# ZYF-02-0-R-8A8K64D4-SCH.net
KiCad netlist of a schematic drawn in EasyEDA
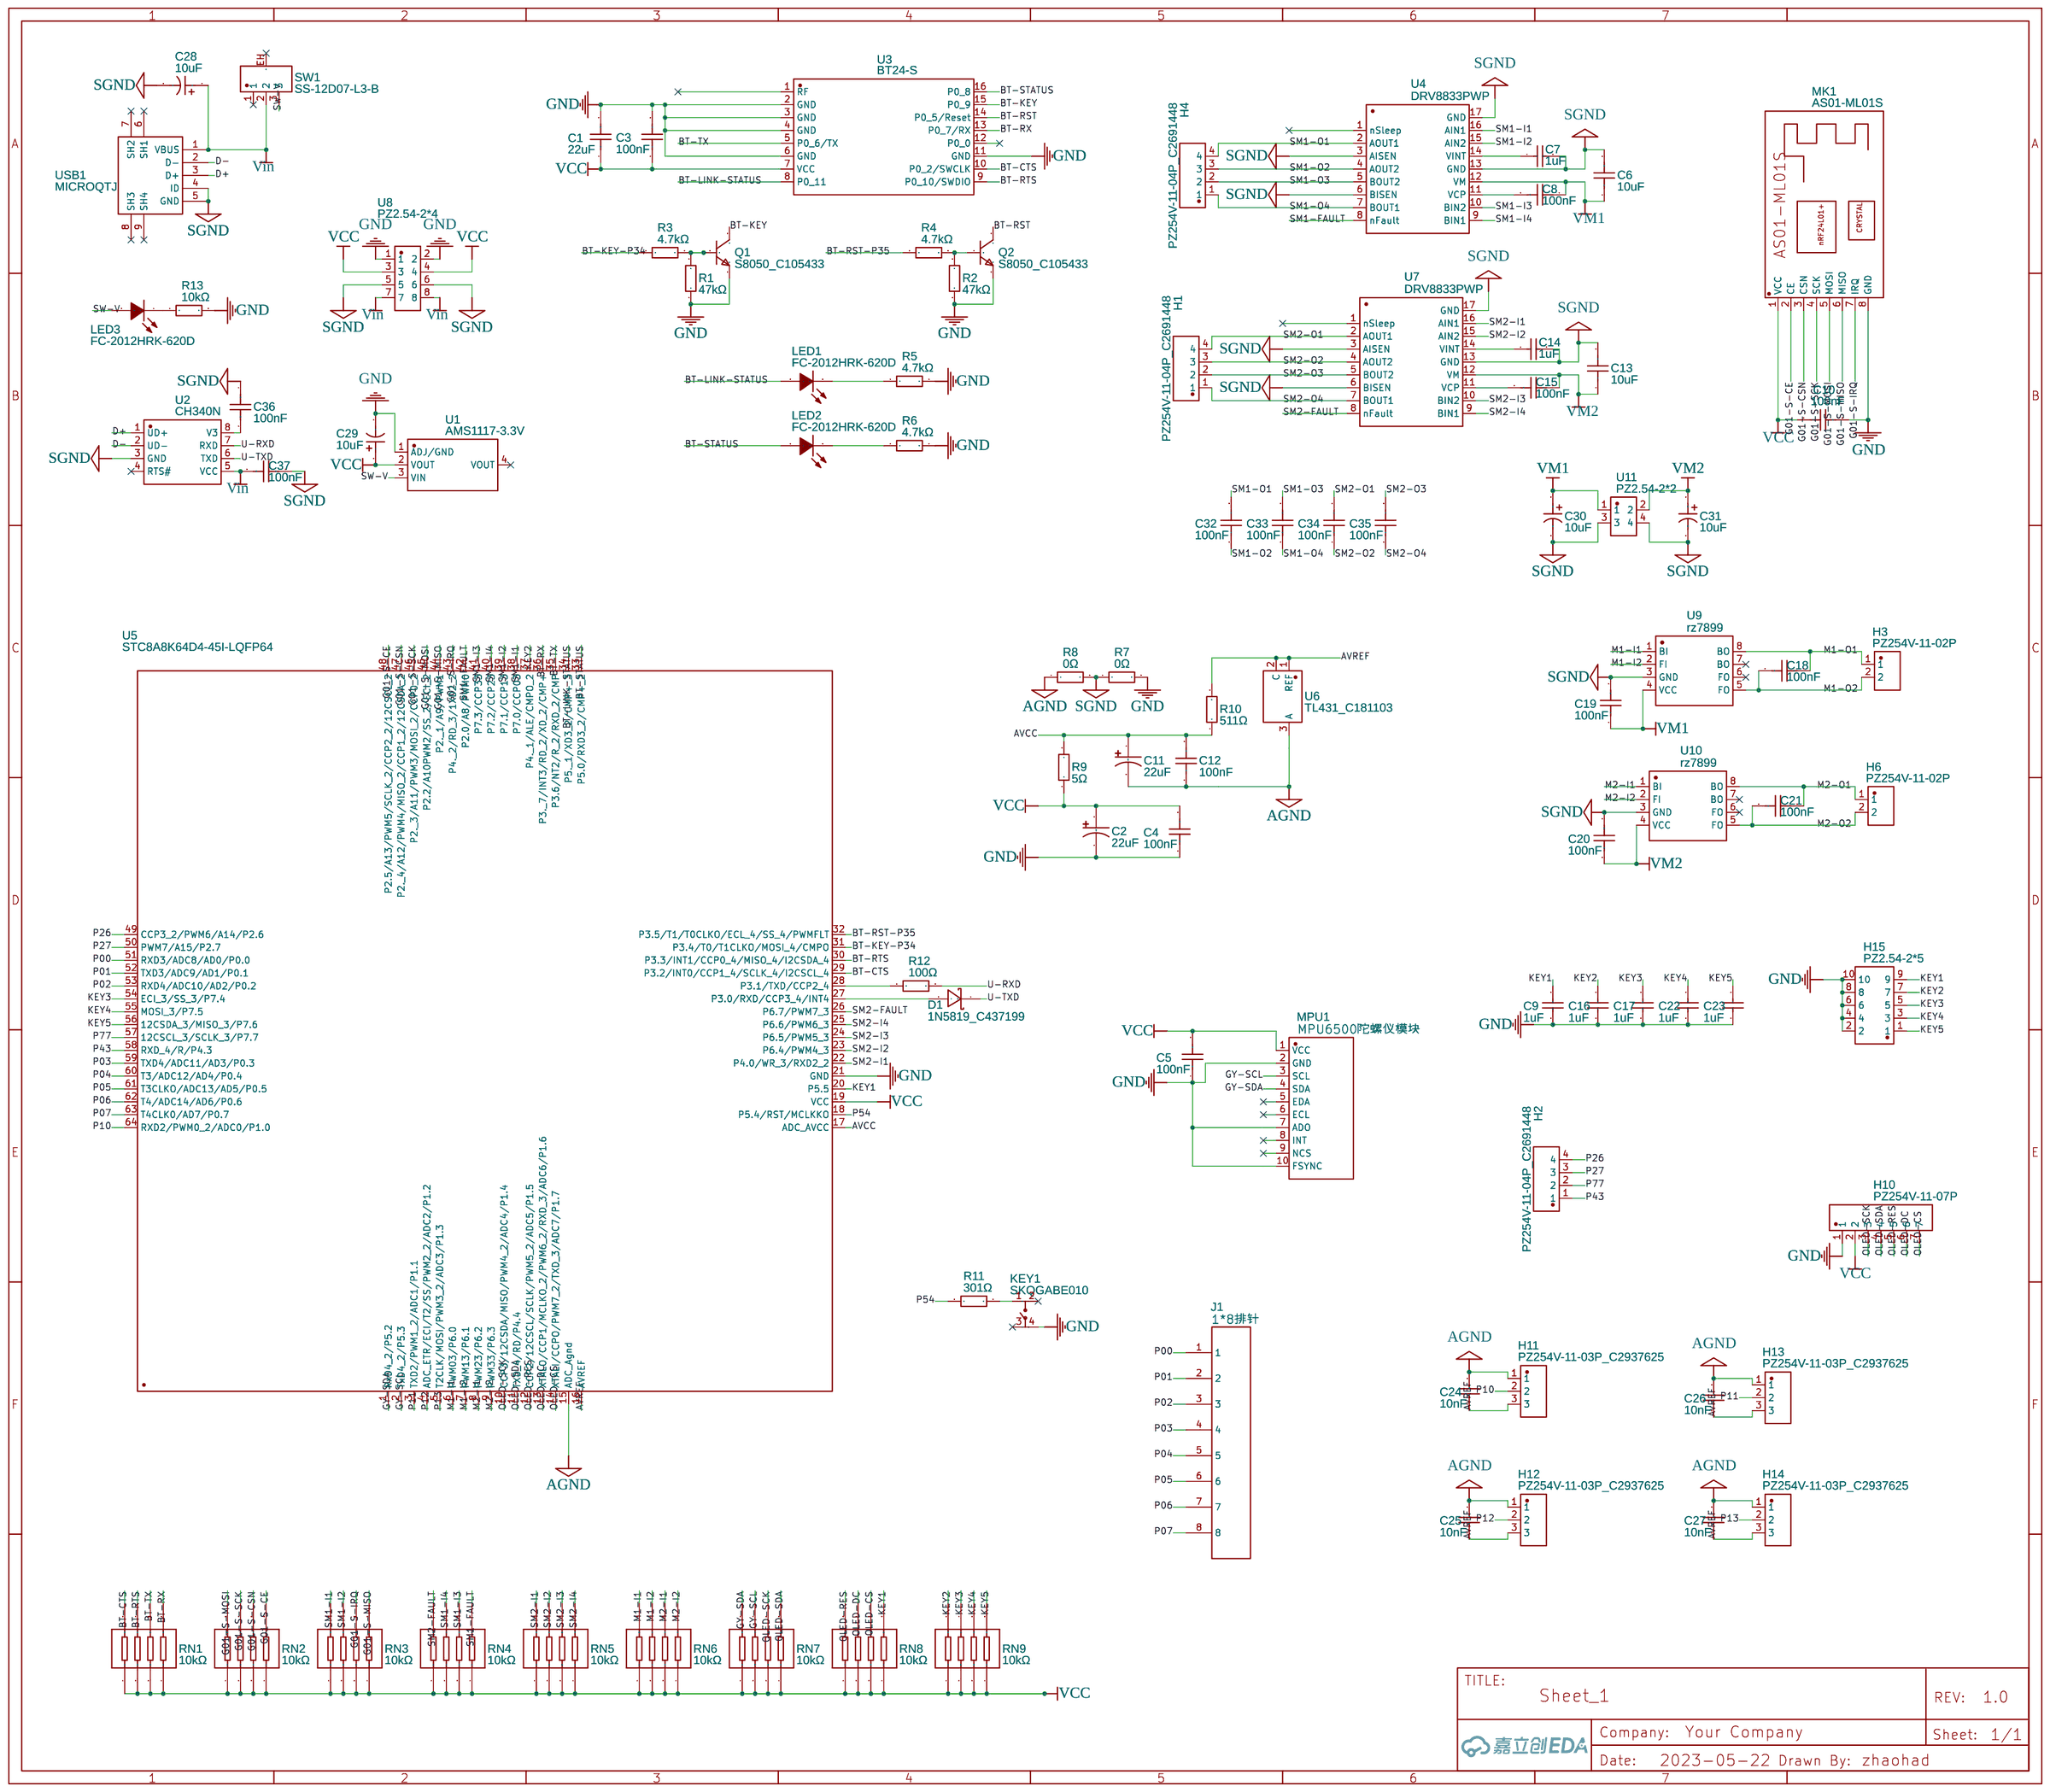
[diagram p0: schematic sheet]

(export (version "E")
  (design (tool "Eeschema 10.0.6"))
  (components
    (comp (ref "C1")
      (value "22uF")
      (fields
        (field (name "BOM_Manufacturer Part") "CL10A226MP8NUNE")
        (field (name "BOM_Supplier Part") "C86295")
      )
      (libsource (lib "") (part "CL10A226MP8NUNE"))
    )
    (comp (ref "C2")
      (value "22uF")
      (fields
        (field (name "BOM_Manufacturer Part") "EEEFTH101XAP")
        (field (name "BOM_Supplier Part") "C165974")
      )
      (libsource (lib "") (part "EEEFTH101XAP"))
    )
    (comp (ref "C3")
      (value "100nF")
      (fields
        (field (name "BOM_Manufacturer Part") "CC0603KRX7R9BB104")
        (field (name "BOM_Supplier Part") "C14663")
      )
      (libsource (lib "") (part "CC0603KRX7R9BB104_2"))
    )
    (comp (ref "C4")
      (value "100nF")
      (fields
        (field (name "BOM_Manufacturer Part") "CC0603KRX7R9BB104")
        (field (name "BOM_Supplier Part") "C14663")
      )
      (libsource (lib "") (part "CC0603KRX7R9BB104_2"))
    )
    (comp (ref "C5")
      (value "100nF")
      (fields
        (field (name "BOM_Manufacturer Part") "CC0603KRX7R9BB104")
        (field (name "BOM_Supplier Part") "C14663")
      )
      (libsource (lib "") (part "CC0603KRX7R9BB104_2"))
    )
    (comp (ref "C6")
      (value "10uF")
      (fields
        (field (name "BOM_Manufacturer Part") "CL10A106MA8NRNC")
        (field (name "BOM_Supplier Part") "C96446")
      )
      (libsource (lib "") (part "CL10A106MA8NRNC"))
    )
    (comp (ref "C7")
      (value "1uF")
      (fields
        (field (name "BOM_Manufacturer Part") "CL10A105KB8NNNC")
        (field (name "BOM_Supplier Part") "C15849")
      )
      (libsource (lib "") (part "CL10A105KB8NNNC_1"))
    )
    (comp (ref "C8")
      (value "100nF")
      (fields
        (field (name "BOM_Manufacturer Part") "CC0603KRX7R9BB104")
        (field (name "BOM_Supplier Part") "C14663")
      )
      (libsource (lib "") (part "CC0603KRX7R9BB104"))
    )
    (comp (ref "C9")
      (value "1uF")
      (fields
        (field (name "BOM_Manufacturer Part") "CL10A105KB8NNNC")
        (field (name "BOM_Supplier Part") "C15849")
      )
      (libsource (lib "") (part "CL10A105KB8NNNC"))
    )
    (comp (ref "C10")
      (value "100nF")
      (fields
        (field (name "BOM_Manufacturer Part") "CC0603KRX7R9BB104")
        (field (name "BOM_Supplier Part") "C14663")
      )
      (libsource (lib "") (part "CC0603KRX7R9BB104"))
    )
    (comp (ref "C11")
      (value "22uF")
      (fields
        (field (name "BOM_Manufacturer Part") "EEEFTH101XAP")
        (field (name "BOM_Supplier Part") "C165974")
      )
      (libsource (lib "") (part "EEEFTH101XAP"))
    )
    (comp (ref "C12")
      (value "100nF")
      (fields
        (field (name "BOM_Manufacturer Part") "CC0603KRX7R9BB104")
        (field (name "BOM_Supplier Part") "C14663")
      )
      (libsource (lib "") (part "CC0603KRX7R9BB104_2"))
    )
    (comp (ref "C13")
      (value "10uF")
      (fields
        (field (name "BOM_Manufacturer Part") "CL10A106MA8NRNC")
        (field (name "BOM_Supplier Part") "C96446")
      )
      (libsource (lib "") (part "CL10A106MA8NRNC"))
    )
    (comp (ref "C14")
      (value "1uF")
      (fields
        (field (name "BOM_Manufacturer Part") "CL10A105KB8NNNC")
        (field (name "BOM_Supplier Part") "C15849")
      )
      (libsource (lib "") (part "CL10A105KB8NNNC_1"))
    )
    (comp (ref "C15")
      (value "100nF")
      (fields
        (field (name "BOM_Manufacturer Part") "CC0603KRX7R9BB104")
        (field (name "BOM_Supplier Part") "C14663")
      )
      (libsource (lib "") (part "CC0603KRX7R9BB104"))
    )
    (comp (ref "C16")
      (value "1uF")
      (fields
        (field (name "BOM_Manufacturer Part") "CL10A105KB8NNNC")
        (field (name "BOM_Supplier Part") "C15849")
      )
      (libsource (lib "") (part "CL10A105KB8NNNC"))
    )
    (comp (ref "C17")
      (value "1uF")
      (fields
        (field (name "BOM_Manufacturer Part") "CL10A105KB8NNNC")
        (field (name "BOM_Supplier Part") "C15849")
      )
      (libsource (lib "") (part "CL10A105KB8NNNC"))
    )
    (comp (ref "C18")
      (value "100nF")
      (fields
        (field (name "BOM_Manufacturer Part") "CC0603KRX7R9BB104")
        (field (name "BOM_Supplier Part") "C14663")
      )
      (libsource (lib "") (part "CC0603KRX7R9BB104"))
    )
    (comp (ref "C19")
      (value "100nF")
      (fields
        (field (name "BOM_Manufacturer Part") "CC0603KRX7R9BB104")
        (field (name "BOM_Supplier Part") "C14663")
      )
      (libsource (lib "") (part "CC0603KRX7R9BB104_2"))
    )
    (comp (ref "C20")
      (value "100nF")
      (fields
        (field (name "BOM_Manufacturer Part") "CC0603KRX7R9BB104")
        (field (name "BOM_Supplier Part") "C14663")
      )
      (libsource (lib "") (part "CC0603KRX7R9BB104_2"))
    )
    (comp (ref "C21")
      (value "100nF")
      (fields
        (field (name "BOM_Manufacturer Part") "CC0603KRX7R9BB104")
        (field (name "BOM_Supplier Part") "C14663")
      )
      (libsource (lib "") (part "CC0603KRX7R9BB104"))
    )
    (comp (ref "C22")
      (value "1uF")
      (fields
        (field (name "BOM_Manufacturer Part") "CL10A105KB8NNNC")
        (field (name "BOM_Supplier Part") "C15849")
      )
      (libsource (lib "") (part "CL10A105KB8NNNC"))
    )
    (comp (ref "C23")
      (value "1uF")
      (fields
        (field (name "BOM_Manufacturer Part") "CL10A105KB8NNNC")
        (field (name "BOM_Supplier Part") "C15849")
      )
      (libsource (lib "") (part "CL10A105KB8NNNC"))
    )
    (comp (ref "C24")
      (value "10nF")
      (fields
        (field (name "BOM_Manufacturer Part") "CL10A105KB8NNNC")
        (field (name "BOM_Supplier Part") "C15849")
      )
      (libsource (lib "") (part "CL10A105KB8NNNC"))
    )
    (comp (ref "C25")
      (value "10nF")
      (fields
        (field (name "BOM_Manufacturer Part") "CL10A105KB8NNNC")
        (field (name "BOM_Supplier Part") "C15849")
      )
      (libsource (lib "") (part "CL10A105KB8NNNC"))
    )
    (comp (ref "C26")
      (value "10nF")
      (fields
        (field (name "BOM_Manufacturer Part") "CL10A105KB8NNNC")
        (field (name "BOM_Supplier Part") "C15849")
      )
      (libsource (lib "") (part "CL10A105KB8NNNC"))
    )
    (comp (ref "C27")
      (value "10nF")
      (fields
        (field (name "BOM_Manufacturer Part") "CL10A105KB8NNNC")
        (field (name "BOM_Supplier Part") "C15849")
      )
      (libsource (lib "") (part "CL10A105KB8NNNC"))
    )
    (comp (ref "C28")
      (value "10uF")
      (fields
        (field (name "BOM_Manufacturer Part") "XT10UF50V90RV0071")
        (field (name "BOM_Supplier Part") "C2992603")
      )
      (libsource (lib "") (part "XT10UF50V90RV0071"))
    )
    (comp (ref "C29")
      (value "10uF")
      (fields
        (field (name "BOM_Manufacturer Part") "XT10UF50V90RV0071")
        (field (name "BOM_Supplier Part") "C2992603")
      )
      (libsource (lib "") (part "XT10UF50V90RV0071_1"))
    )
    (comp (ref "C30")
      (value "10uF")
      (fields
        (field (name "BOM_Manufacturer Part") "XT10UF50V90RV0071")
        (field (name "BOM_Supplier Part") "C2992603")
      )
      (libsource (lib "") (part "XT10UF50V90RV0071_2"))
    )
    (comp (ref "C31")
      (value "10uF")
      (fields
        (field (name "BOM_Manufacturer Part") "XT10UF50V90RV0071")
        (field (name "BOM_Supplier Part") "C2992603")
      )
      (libsource (lib "") (part "XT10UF50V90RV0071_2"))
    )
    (comp (ref "C32")
      (value "100nF")
      (fields
        (field (name "BOM_Manufacturer Part") "CC0603KRX7R9BB104")
        (field (name "BOM_Supplier Part") "C14663")
      )
      (libsource (lib "") (part "CC0603KRX7R9BB104_2"))
    )
    (comp (ref "C33")
      (value "100nF")
      (fields
        (field (name "BOM_Manufacturer Part") "CC0603KRX7R9BB104")
        (field (name "BOM_Supplier Part") "C14663")
      )
      (libsource (lib "") (part "CC0603KRX7R9BB104_2"))
    )
    (comp (ref "C34")
      (value "100nF")
      (fields
        (field (name "BOM_Manufacturer Part") "CC0603KRX7R9BB104")
        (field (name "BOM_Supplier Part") "C14663")
      )
      (libsource (lib "") (part "CC0603KRX7R9BB104_2"))
    )
    (comp (ref "C35")
      (value "100nF")
      (fields
        (field (name "BOM_Manufacturer Part") "CC0603KRX7R9BB104")
        (field (name "BOM_Supplier Part") "C14663")
      )
      (libsource (lib "") (part "CC0603KRX7R9BB104_2"))
    )
    (comp (ref "C36")
      (value "100nF")
      (fields
        (field (name "BOM_Manufacturer Part") "CC0603KRX7R9BB104")
        (field (name "BOM_Supplier Part") "C14663")
      )
      (libsource (lib "") (part "CC0603KRX7R9BB104_1"))
    )
    (comp (ref "C37")
      (value "100nF")
      (fields
        (field (name "BOM_Manufacturer Part") "CC0603KRX7R9BB104")
        (field (name "BOM_Supplier Part") "C14663")
      )
      (libsource (lib "") (part "CC0603KRX7R9BB104"))
    )
    (comp (ref "D1")
      (value "1N5819_C437199")
      (fields (field (name "BOM_Manufacturer Part") "1N5819") (field (name "BOM_Supplier Part") "C437199"))
      (libsource (lib "") (part "1N5819_C437199"))
    )
    (comp (ref "H1")
      (value "PZ254V-11-04P_C2691448")
      (fields
        (field (name "BOM_Manufacturer Part") "PZ254V-11-04P")
        (field (name "BOM_Supplier Part") "C2691448")
      )
      (libsource (lib "") (part "PZ254V-11-04P_C2691448"))
    )
    (comp (ref "H2")
      (value "PZ254V-11-04P_C2691448")
      (fields
        (field (name "BOM_Manufacturer Part") "PZ254V-11-04P")
        (field (name "BOM_Supplier Part") "C2691448")
      )
      (libsource (lib "") (part "PZ254V-11-04P_C2691448"))
    )
    (comp (ref "H3")
      (value "PZ254V-11-02P")
      (fields (field (name "BOM_Supplier Part") "C492401"))
      (libsource (lib "") (part "PZ254V-11-02P"))
    )
    (comp (ref "H4")
      (value "PZ254V-11-04P_C2691448")
      (fields
        (field (name "BOM_Manufacturer Part") "PZ254V-11-04P")
        (field (name "BOM_Supplier Part") "C2691448")
      )
      (libsource (lib "") (part "PZ254V-11-04P_C2691448"))
    )
    (comp (ref "H6")
      (value "PZ254V-11-02P")
      (fields (field (name "BOM_Supplier Part") "C492401"))
      (libsource (lib "") (part "PZ254V-11-02P"))
    )
    (comp (ref "H10")
      (value "PZ254V-11-07P")
      (fields (field (name "BOM_Supplier Part") "C492406"))
      (libsource (lib "") (part "PZ254V-11-07P"))
    )
    (comp (ref "H11")
      (value "PZ254V-11-03P_C2937625")
      (fields
        (field (name "BOM_Manufacturer Part") "PZ254V-11-03P")
        (field (name "BOM_Supplier Part") "C2937625")
      )
      (libsource (lib "") (part "PZ254V-11-03P_C2937625"))
    )
    (comp (ref "H12")
      (value "PZ254V-11-03P_C2937625")
      (fields
        (field (name "BOM_Manufacturer Part") "PZ254V-11-03P")
        (field (name "BOM_Supplier Part") "C2937625")
      )
      (libsource (lib "") (part "PZ254V-11-03P_C2937625"))
    )
    (comp (ref "H13")
      (value "PZ254V-11-03P_C2937625")
      (fields
        (field (name "BOM_Manufacturer Part") "PZ254V-11-03P")
        (field (name "BOM_Supplier Part") "C2937625")
      )
      (libsource (lib "") (part "PZ254V-11-03P_C2937625"))
    )
    (comp (ref "H14")
      (value "PZ254V-11-03P_C2937625")
      (fields
        (field (name "BOM_Manufacturer Part") "PZ254V-11-03P")
        (field (name "BOM_Supplier Part") "C2937625")
      )
      (libsource (lib "") (part "PZ254V-11-03P_C2937625"))
    )
    (comp (ref "H15")
      (value "PZ2.54-2*5")
      (fields (field (name "BOM_Supplier Part") "C5156677"))
      (libsource (lib "") (part "PZ2.54-2*5"))
    )
    (comp (ref "J1")
      (value "1*8排针")
      (fields (field (name "BOM_Manufacturer Part") "2.54-1*8") (field (name "BOM_Supplier Part") "C5156616"))
      (libsource (lib "") (part "1*8排针"))
    )
    (comp (ref "KEY1")
      (value "SKQGABE010")
      (fields (field (name "BOM_Supplier Part") "C115351"))
      (libsource (lib "") (part "SKQGABE010"))
    )
    (comp (ref "LED1")
      (value "FC-2012HRK-620D")
      (fields (field (name "BOM_Manufacturer Part") "NCD0805R1") (field (name "BOM_Supplier Part") "C84256"))
      (libsource (lib "") (part "FC-2012HRK-620D"))
    )
    (comp (ref "LED2")
      (value "FC-2012HRK-620D")
      (fields (field (name "BOM_Manufacturer Part") "NCD0805R1") (field (name "BOM_Supplier Part") "C84256"))
      (libsource (lib "") (part "FC-2012HRK-620D"))
    )
    (comp (ref "LED3")
      (value "FC-2012HRK-620D")
      (fields (field (name "BOM_Manufacturer Part") "NCD0805R1") (field (name "BOM_Supplier Part") "C84256"))
      (libsource (lib "") (part "FC-2012HRK-620D"))
    )
    (comp (ref "MK1")
      (value "AS01-ML01S")
      (fields (field (name "BOM_Supplier Part") "C84802"))
      (libsource (lib "") (part "AS01-ML01S"))
    )
    (comp (ref "MPU1") (value "MPU6500陀螺仪模块") (libsource (lib "") (part "MPU6500陀螺仪模块")))
    (comp (ref "Q1")
      (value "S8050_C105433")
      (fields (field (name "BOM_Manufacturer Part") "S8050") (field (name "BOM_Supplier Part") "C105433"))
      (libsource (lib "") (part "S8050_C105433"))
    )
    (comp (ref "Q2")
      (value "S8050_C105433")
      (fields (field (name "BOM_Manufacturer Part") "S8050") (field (name "BOM_Supplier Part") "C105433"))
      (libsource (lib "") (part "S8050_C105433"))
    )
    (comp (ref "R1")
      (value "47kΩ")
      (fields
        (field (name "BOM_Manufacturer Part") "0603WAF4702T5E")
        (field (name "BOM_Supplier Part") "C25819")
      )
      (libsource (lib "") (part "0603WAF4702T5E"))
    )
    (comp (ref "R2")
      (value "47kΩ")
      (fields
        (field (name "BOM_Manufacturer Part") "0603WAF4702T5E")
        (field (name "BOM_Supplier Part") "C25819")
      )
      (libsource (lib "") (part "0603WAF4702T5E"))
    )
    (comp (ref "R3")
      (value "4.7kΩ")
      (fields
        (field (name "BOM_Manufacturer Part") "0603WAF4701T5E")
        (field (name "BOM_Supplier Part") "C23162")
      )
      (libsource (lib "") (part "0603WAF4701T5E"))
    )
    (comp (ref "R4")
      (value "4.7kΩ")
      (fields
        (field (name "BOM_Manufacturer Part") "0603WAF4701T5E")
        (field (name "BOM_Supplier Part") "C23162")
      )
      (libsource (lib "") (part "0603WAF4701T5E"))
    )
    (comp (ref "R5")
      (value "4.7kΩ")
      (fields
        (field (name "BOM_Manufacturer Part") "0603WAF4701T5E")
        (field (name "BOM_Supplier Part") "C23162")
      )
      (libsource (lib "") (part "0603WAF4701T5E"))
    )
    (comp (ref "R6")
      (value "4.7kΩ")
      (fields
        (field (name "BOM_Manufacturer Part") "0603WAF4701T5E")
        (field (name "BOM_Supplier Part") "C23162")
      )
      (libsource (lib "") (part "0603WAF4701T5E"))
    )
    (comp (ref "R7")
      (value "0Ω")
      (fields
        (field (name "BOM_Manufacturer Part") "0603WAF0000T5E")
        (field (name "BOM_Supplier Part") "C21189")
      )
      (libsource (lib "") (part "0603WAF0000T5E"))
    )
    (comp (ref "R8")
      (value "0Ω")
      (fields
        (field (name "BOM_Manufacturer Part") "0603WAF0000T5E")
        (field (name "BOM_Supplier Part") "C21189")
      )
      (libsource (lib "") (part "0603WAF0000T5E"))
    )
    (comp (ref "R9")
      (value "5Ω")
      (fields
        (field (name "BOM_Manufacturer Part") "0603WAF4701T5E")
        (field (name "BOM_Supplier Part") "C23162")
      )
      (libsource (lib "") (part "0603WAF4701T5E_1"))
    )
    (comp (ref "R10")
      (value "511Ω")
      (fields
        (field (name "BOM_Manufacturer Part") "0603WAF5100T5E")
        (field (name "BOM_Supplier Part") "C23193")
      )
      (libsource (lib "") (part "0603WAF5100T5E"))
    )
    (comp (ref "R11")
      (value "301Ω")
      (fields
        (field (name "BOM_Manufacturer Part") "0603WAF4701T5E")
        (field (name "BOM_Supplier Part") "C23162")
      )
      (libsource (lib "") (part "0603WAF4701T5E_2"))
    )
    (comp (ref "R12")
      (value "100Ω")
      (fields
        (field (name "BOM_Manufacturer Part") "0603WAF4701T5E")
        (field (name "BOM_Supplier Part") "C23162")
      )
      (libsource (lib "") (part "0603WAF4701T5E"))
    )
    (comp (ref "R13")
      (value "10kΩ")
      (fields
        (field (name "BOM_Manufacturer Part") "0603WAF4701T5E")
        (field (name "BOM_Supplier Part") "C23162")
      )
      (libsource (lib "") (part "0603WAF4701T5E"))
    )
    (comp (ref "RN1")
      (value "10kΩ")
      (fields
        (field (name "BOM_Manufacturer Part") "4D03WGJ0103T5E")
        (field (name "BOM_Supplier Part") "C29718")
      )
      (libsource (lib "") (part "4D03WGJ0103T5E"))
    )
    (comp (ref "RN2")
      (value "10kΩ")
      (fields
        (field (name "BOM_Manufacturer Part") "4D03WGJ0103T5E")
        (field (name "BOM_Supplier Part") "C29718")
      )
      (libsource (lib "") (part "4D03WGJ0103T5E"))
    )
    (comp (ref "RN3")
      (value "10kΩ")
      (fields
        (field (name "BOM_Manufacturer Part") "4D03WGJ0103T5E")
        (field (name "BOM_Supplier Part") "C29718")
      )
      (libsource (lib "") (part "4D03WGJ0103T5E"))
    )
    (comp (ref "RN4")
      (value "10kΩ")
      (fields
        (field (name "BOM_Manufacturer Part") "4D03WGJ0103T5E")
        (field (name "BOM_Supplier Part") "C29718")
      )
      (libsource (lib "") (part "4D03WGJ0103T5E"))
    )
    (comp (ref "RN5")
      (value "10kΩ")
      (fields
        (field (name "BOM_Manufacturer Part") "4D03WGJ0103T5E")
        (field (name "BOM_Supplier Part") "C29718")
      )
      (libsource (lib "") (part "4D03WGJ0103T5E"))
    )
    (comp (ref "RN6")
      (value "10kΩ")
      (fields
        (field (name "BOM_Manufacturer Part") "4D03WGJ0103T5E")
        (field (name "BOM_Supplier Part") "C29718")
      )
      (libsource (lib "") (part "4D03WGJ0103T5E"))
    )
    (comp (ref "RN7")
      (value "10kΩ")
      (fields
        (field (name "BOM_Manufacturer Part") "4D03WGJ0103T5E")
        (field (name "BOM_Supplier Part") "C29718")
      )
      (libsource (lib "") (part "4D03WGJ0103T5E"))
    )
    (comp (ref "RN8")
      (value "10kΩ")
      (fields
        (field (name "BOM_Manufacturer Part") "4D03WGJ0103T5E")
        (field (name "BOM_Supplier Part") "C29718")
      )
      (libsource (lib "") (part "4D03WGJ0103T5E"))
    )
    (comp (ref "RN9")
      (value "10kΩ")
      (fields
        (field (name "BOM_Manufacturer Part") "4D03WGJ0103T5E")
        (field (name "BOM_Supplier Part") "C29718")
      )
      (libsource (lib "") (part "4D03WGJ0103T5E"))
    )
    (comp (ref "SW1")
      (value "SS-12D07-L3-B")
      (fields
        (field (name "BOM_Manufacturer Part") "SS12D07L3B")
        (field (name "BOM_Supplier Part") "C480343")
      )
      (libsource (lib "") (part "SS-12D07-L3-B"))
    )
    (comp (ref "U1")
      (value "AMS1117-3.3V")
      (fields (field (name "BOM_Supplier Part") "C2688239"))
      (libsource (lib "") (part "AMS1117-3.3V"))
    )
    (comp (ref "U2")
      (value "CH340N")
      (fields (field (name "BOM_Supplier Part") "C506813"))
      (libsource (lib "") (part "CH340N"))
    )
    (comp (ref "U3")
      (value "BT24-S")
      (fields (field (name "BOM_Supplier Part") "C9900007879"))
      (libsource (lib "") (part "BT24-S"))
    )
    (comp (ref "U4")
      (value "DRV8833PWP")
      (fields
        (field (name "BOM_Manufacturer Part") "DRV8833PWPR")
        (field (name "BOM_Supplier Part") "C50506")
      )
      (libsource (lib "") (part "DRV8833PWP"))
    )
    (comp (ref "U5")
      (value "STC8A8K64D4-45I-LQFP64")
      (fields (field (name "BOM_Supplier Part") "C9900000181"))
      (libsource (lib "") (part "STC8A8K64D4-45I-LQFP64"))
    )
    (comp (ref "U6")
      (value "TL431_C181103")
      (fields (field (name "BOM_Manufacturer Part") "TL431") (field (name "BOM_Supplier Part") "C181103"))
      (libsource (lib "") (part "TL431_C181103"))
    )
    (comp (ref "U7")
      (value "DRV8833PWP")
      (fields
        (field (name "BOM_Manufacturer Part") "DRV8833PWPR")
        (field (name "BOM_Supplier Part") "C50506")
      )
      (libsource (lib "") (part "DRV8833PWP"))
    )
    (comp (ref "U8")
      (value "PZ2.54-2*4")
      (fields (field (name "BOM_Supplier Part") "C5156676"))
      (libsource (lib "") (part "PZ2.54-2*4"))
    )
    (comp (ref "U9")
      (value "rz7899")
      (fields (field (name "BOM_Supplier Part") "C92373"))
      (libsource (lib "") (part "rz7899"))
    )
    (comp (ref "U10")
      (value "rz7899")
      (fields (field (name "BOM_Supplier Part") "C92373"))
      (libsource (lib "") (part "rz7899"))
    )
    (comp (ref "U11")
      (value "PZ2.54-2*2")
      (fields (field (name "BOM_Supplier Part") "C5156675"))
      (libsource (lib "") (part "PZ2.54-2*2"))
    )
    (comp (ref "USB1")
      (value "MICROQTJ")
      (fields (field (name "BOM_Manufacturer Part") "MicroQTJ") (field (name "BOM_Supplier Part") "C404968"))
      (libsource (lib "") (part "MICROQTJ"))
    )
  )
  (nets
    (net (code "1") (name "/AVCC") (class "Default")
      (node (ref "C11") (pin "1") (pinfunction "1_1") (pintype "unspecified"))
      (node (ref "C12") (pin "2") (pinfunction "2_2") (pintype "unspecified"))
      (node (ref "R10") (pin "1") (pinfunction "1_1") (pintype "input"))
      (node (ref "R9") (pin "2") (pinfunction "2_2") (pintype "input"))
      (node (ref "U5") (pin "17") (pinfunction "ADC_AVCC_17") (pintype "unspecified"))
    )
    (net (code "2") (name "/AVREF") (class "Default")
      (node (ref "C24") (pin "1") (pinfunction "1_1") (pintype "input"))
      (node (ref "C25") (pin "1") (pinfunction "1_1") (pintype "input"))
      (node (ref "C26") (pin "1") (pinfunction "1_1") (pintype "input"))
      (node (ref "C27") (pin "1") (pinfunction "1_1") (pintype "input"))
      (node (ref "H11") (pin "3") (pinfunction "3_3") (pintype "unspecified"))
      (node (ref "H12") (pin "3") (pinfunction "3_3") (pintype "unspecified"))
      (node (ref "H13") (pin "3") (pinfunction "3_3") (pintype "unspecified"))
      (node (ref "H14") (pin "3") (pinfunction "3_3") (pintype "unspecified"))
      (node (ref "R10") (pin "2") (pinfunction "2_2") (pintype "input"))
      (node (ref "U5") (pin "16") (pinfunction "AVREF_16") (pintype "unspecified"))
      (node (ref "U6") (pin "1") (pinfunction "REF_1") (pintype "unspecified"))
      (node (ref "U6") (pin "2") (pinfunction "C_2") (pintype "unspecified"))
    )
    (net (code "3") (name "/BT-CTS") (class "Default")
      (node (ref "RN1") (pin "8") (pinfunction "8_8") (pintype "input"))
      (node (ref "U3") (pin "10") (pinfunction "P0_2/SWCLK_10") (pintype "unspecified"))
      (node (ref "U5") (pin "29") (pinfunction "P3.2/INT0/CCP1_4/SCLK_4/I2CSCL_4_29") (pintype "unspecified"))
    )
    (net (code "4") (name "/BT-KEY") (class "Default")
      (node (ref "Q1") (pin "3") (pinfunction "3_3") (pintype "input"))
      (node (ref "U3") (pin "15") (pinfunction "P0_9_15") (pintype "unspecified"))
    )
    (net (code "5") (name "/BT-KEY-P34") (class "Default")
      (node (ref "R3") (pin "1") (pinfunction "1_1") (pintype "input"))
      (node (ref "U5") (pin "31") (pinfunction "P3.4/T0/T1CLKO/MOSI_4/CMPO_31") (pintype "unspecified"))
    )
    (net (code "6") (name "/BT-LINK-STATUS") (class "Default")
      (node (ref "LED1") (pin "2") (pinfunction "+_2") (pintype "unspecified"))
      (node (ref "U3") (pin "8") (pinfunction "P0_11_8") (pintype "unspecified"))
      (node (ref "U5") (pin "34") (pinfunction "P5._1/XD3_2/CMP+_3_34") (pintype "unspecified"))
    )
    (net (code "7") (name "/BT-RST") (class "Default")
      (node (ref "Q2") (pin "3") (pinfunction "3_3") (pintype "input"))
      (node (ref "U3") (pin "14") (pinfunction "P0_5/Reset_14") (pintype "unspecified"))
    )
    (net (code "8") (name "/BT-RST-P35") (class "Default")
      (node (ref "R4") (pin "1") (pinfunction "1_1") (pintype "input"))
      (node (ref "U5") (pin "32") (pinfunction "P3.5/T1/T0CLKO/ECL_4/SS_4/PWMFLT_32") (pintype "unspecified"))
    )
    (net (code "9") (name "/BT-RTS") (class "Default")
      (node (ref "RN1") (pin "7") (pinfunction "7_7") (pintype "input"))
      (node (ref "U3") (pin "9") (pinfunction "P0_10/SWDIO_9") (pintype "unspecified"))
      (node (ref "U5") (pin "30") (pinfunction "P3.3/INT1/CCP0_4/MISO_4/I2CSDA_4_30") (pintype "unspecified"))
    )
    (net (code "10") (name "/BT-RX") (class "Default")
      (node (ref "RN1") (pin "5") (pinfunction "5_5") (pintype "input"))
      (node (ref "U3") (pin "13") (pinfunction "P0_7/RX_13") (pintype "unspecified"))
      (node (ref "U5") (pin "36") (pinfunction "P3._7/INT3/RD_2/XD_2/CMP+_36") (pintype "unspecified"))
    )
    (net (code "11") (name "/BT-STATUS") (class "Default")
      (node (ref "LED2") (pin "2") (pinfunction "+_2") (pintype "unspecified"))
      (node (ref "U3") (pin "16") (pinfunction "P0_8_16") (pintype "unspecified"))
      (node (ref "U5") (pin "33") (pinfunction "P5.0/RXD3_2/CMP+_2_33") (pintype "unspecified"))
    )
    (net (code "12") (name "/BT-TX") (class "Default")
      (node (ref "RN1") (pin "6") (pinfunction "6_6") (pintype "input"))
      (node (ref "U3") (pin "5") (pinfunction "P0_6/TX_5") (pintype "unspecified"))
      (node (ref "U5") (pin "35") (pinfunction "P3.6/NT2/R_2/RXD_2/CMP_35") (pintype "unspecified"))
    )
    (net (code "13") (name "/D+") (class "Default")
      (node (ref "U2") (pin "1") (pinfunction "UD+_1") (pintype "unspecified"))
      (node (ref "USB1") (pin "3") (pinfunction "D+_3") (pintype "unspecified"))
    )
    (net (code "14") (name "/D-") (class "Default")
      (node (ref "U2") (pin "2") (pinfunction "UD-_2") (pintype "unspecified"))
      (node (ref "USB1") (pin "2") (pinfunction "D-_2") (pintype "unspecified"))
    )
    (net (code "15") (name "/G01-S-CE") (class "Default")
      (node (ref "MK1") (pin "2") (pinfunction "CE_2") (pintype "unspecified"))
      (node (ref "RN2") (pin "5") (pinfunction "5_5") (pintype "input"))
      (node (ref "U5") (pin "48") (pinfunction "P2.5/A13/PWM5/SCLK_2/CCP2_2/12CSCL_2_48") (pintype "unspecified"))
    )
    (net (code "16") (name "/G01-S-CSN") (class "Default")
      (node (ref "MK1") (pin "3") (pinfunction "CSN_3") (pintype "unspecified"))
      (node (ref "RN2") (pin "6") (pinfunction "6_6") (pintype "input"))
      (node (ref "U5") (pin "47") (pinfunction "P2._4/A12/PWM4/MISO_2/CCP1_2/12CSDA_2_47") (pintype "unspecified"))
    )
    (net (code "17") (name "/G01-S-IRQ") (class "Default")
      (node (ref "MK1") (pin "7") (pinfunction "IRQ_7") (pintype "unspecified"))
      (node (ref "RN3") (pin "6") (pinfunction "6_6") (pintype "input"))
      (node (ref "U5") (pin "43") (pinfunction "P4._2/RD_3/1XD2_2_43") (pintype "unspecified"))
    )
    (net (code "18") (name "/G01-S-MISO") (class "Default")
      (node (ref "MK1") (pin "6") (pinfunction "MISO_6") (pintype "unspecified"))
      (node (ref "RN3") (pin "5") (pinfunction "5_5") (pintype "input"))
      (node (ref "U5") (pin "44") (pinfunction "P2._1/A9/PWM1_44") (pintype "unspecified"))
    )
    (net (code "19") (name "/G01-S-MOSI") (class "Default")
      (node (ref "MK1") (pin "5") (pinfunction "MOSI_5") (pintype "unspecified"))
      (node (ref "RN2") (pin "8") (pinfunction "8_8") (pintype "input"))
      (node (ref "U5") (pin "45") (pinfunction "P2.2/A10PWM2/SS_2/ECI_2_45") (pintype "unspecified"))
    )
    (net (code "20") (name "/G01-S-SCK") (class "Default")
      (node (ref "MK1") (pin "4") (pinfunction "SCK_4") (pintype "unspecified"))
      (node (ref "RN2") (pin "7") (pinfunction "7_7") (pintype "input"))
      (node (ref "U5") (pin "46") (pinfunction "P2._3/A11/PWM3/MOSI_2/CCP0_2_46") (pintype "unspecified"))
    )
    (net (code "21") (name "/GY-SCL") (class "Default")
      (node (ref "MPU1") (pin "3") (pinfunction "SCL_3") (pintype "unspecified"))
      (node (ref "RN7") (pin "7") (pinfunction "7_7") (pintype "input"))
      (node (ref "U5") (pin "2") (pinfunction "TxD4_2/P5.3_2") (pintype "unspecified"))
    )
    (net (code "22") (name "/GY-SDA") (class "Default")
      (node (ref "MPU1") (pin "4") (pinfunction "SDA_4") (pintype "unspecified"))
      (node (ref "RN7") (pin "8") (pinfunction "8_8") (pintype "input"))
      (node (ref "U5") (pin "1") (pinfunction "RxD4_2/P5.2_1") (pintype "unspecified"))
    )
    (net (code "23") (name "/KEY1") (class "Default")
      (node (ref "C9") (pin "2") (pinfunction "2_2") (pintype "input"))
      (node (ref "H15") (pin "9") (pinfunction "9_9") (pintype "unspecified"))
      (node (ref "RN8") (pin "5") (pinfunction "5_5") (pintype "input"))
      (node (ref "U5") (pin "20") (pinfunction "P5.5_20") (pintype "unspecified"))
    )
    (net (code "24") (name "/KEY2") (class "Default")
      (node (ref "C16") (pin "2") (pinfunction "2_2") (pintype "input"))
      (node (ref "H15") (pin "7") (pinfunction "7_7") (pintype "unspecified"))
      (node (ref "RN9") (pin "8") (pinfunction "8_8") (pintype "input"))
      (node (ref "U5") (pin "37") (pinfunction "P4._1/ALE/CMPO_2_37") (pintype "unspecified"))
    )
    (net (code "25") (name "/KEY3") (class "Default")
      (node (ref "C17") (pin "2") (pinfunction "2_2") (pintype "input"))
      (node (ref "H15") (pin "5") (pinfunction "5_5") (pintype "unspecified"))
      (node (ref "RN9") (pin "7") (pinfunction "7_7") (pintype "input"))
      (node (ref "U5") (pin "54") (pinfunction "ECI_3/SS_3/P7.4_54") (pintype "unspecified"))
    )
    (net (code "26") (name "/KEY4") (class "Default")
      (node (ref "C22") (pin "2") (pinfunction "2_2") (pintype "input"))
      (node (ref "H15") (pin "3") (pinfunction "3_3") (pintype "unspecified"))
      (node (ref "RN9") (pin "6") (pinfunction "6_6") (pintype "input"))
      (node (ref "U5") (pin "55") (pinfunction "MOSI_3/P7.5_55") (pintype "unspecified"))
    )
    (net (code "27") (name "/KEY5") (class "Default")
      (node (ref "C23") (pin "2") (pinfunction "2_2") (pintype "input"))
      (node (ref "H15") (pin "1") (pinfunction "1_1") (pintype "unspecified"))
      (node (ref "RN9") (pin "5") (pinfunction "5_5") (pintype "input"))
      (node (ref "U5") (pin "56") (pinfunction "12CSDA_3/MISO_3/P7.6_56") (pintype "unspecified"))
    )
    (net (code "28") (name "/M1-I1") (class "Default")
      (node (ref "RN6") (pin "8") (pinfunction "8_8") (pintype "input"))
      (node (ref "U5") (pin "6") (pinfunction "PWM03/P6.0_6") (pintype "unspecified"))
      (node (ref "U9") (pin "1") (pinfunction "BI_1") (pintype "unspecified"))
    )
    (net (code "29") (name "/M1-I2") (class "Default")
      (node (ref "RN6") (pin "7") (pinfunction "7_7") (pintype "input"))
      (node (ref "U5") (pin "7") (pinfunction "PWM13/P6.1_7") (pintype "unspecified"))
      (node (ref "U9") (pin "2") (pinfunction "FI_2") (pintype "unspecified"))
    )
    (net (code "30") (name "/M1-O1") (class "Default")
      (node (ref "C18") (pin "1") (pinfunction "1_1") (pintype "unspecified"))
      (node (ref "H3") (pin "1") (pinfunction "1_1") (pintype "unspecified"))
      (node (ref "U9") (pin "8") (pinfunction "BO_8") (pintype "unspecified"))
    )
    (net (code "31") (name "/M1-O2") (class "Default")
      (node (ref "C18") (pin "2") (pinfunction "2_2") (pintype "unspecified"))
      (node (ref "H3") (pin "2") (pinfunction "2_2") (pintype "unspecified"))
      (node (ref "U9") (pin "5") (pinfunction "FO_5") (pintype "unspecified"))
    )
    (net (code "32") (name "/M2-I1") (class "Default")
      (node (ref "RN6") (pin "6") (pinfunction "6_6") (pintype "input"))
      (node (ref "U10") (pin "1") (pinfunction "BI_1") (pintype "unspecified"))
      (node (ref "U5") (pin "8") (pinfunction "PWM23/P6.2_8") (pintype "unspecified"))
    )
    (net (code "33") (name "/M2-I2") (class "Default")
      (node (ref "RN6") (pin "5") (pinfunction "5_5") (pintype "input"))
      (node (ref "U10") (pin "2") (pinfunction "FI_2") (pintype "unspecified"))
      (node (ref "U5") (pin "9") (pinfunction "PWM33/P6.3_9") (pintype "unspecified"))
    )
    (net (code "34") (name "/M2-O1") (class "Default")
      (node (ref "C21") (pin "1") (pinfunction "1_1") (pintype "unspecified"))
      (node (ref "H6") (pin "1") (pinfunction "1_1") (pintype "unspecified"))
      (node (ref "U10") (pin "8") (pinfunction "BO_8") (pintype "unspecified"))
    )
    (net (code "35") (name "/M2-O2") (class "Default")
      (node (ref "C21") (pin "2") (pinfunction "2_2") (pintype "unspecified"))
      (node (ref "H6") (pin "2") (pinfunction "2_2") (pintype "unspecified"))
      (node (ref "U10") (pin "5") (pinfunction "FO_5") (pintype "unspecified"))
    )
    (net (code "36") (name "/OLED-CS") (class "Default")
      (node (ref "H10") (pin "7") (pinfunction "7_7") (pintype "unspecified"))
      (node (ref "RN8") (pin "6") (pinfunction "6_6") (pintype "input"))
      (node (ref "U5") (pin "14") (pinfunction "XTALI/CCPO/PWM7_2/TXD_3/ADC7/P1.7_14") (pintype "unspecified"))
    )
    (net (code "37") (name "/OLED-DC") (class "Default")
      (node (ref "H10") (pin "6") (pinfunction "6_6") (pintype "unspecified"))
      (node (ref "RN8") (pin "7") (pinfunction "7_7") (pintype "input"))
      (node (ref "U5") (pin "13") (pinfunction "XTALO/CCP1/MCLKO_2/PWM6_2/RXD_3/ADC6/P1.6_13") (pintype "unspecified"))
    )
    (net (code "38") (name "/OLED-RES") (class "Default")
      (node (ref "H10") (pin "5") (pinfunction "5_5") (pintype "unspecified"))
      (node (ref "RN8") (pin "8") (pinfunction "8_8") (pintype "input"))
      (node (ref "U5") (pin "12") (pinfunction "CCP2/12CSCL/SCLK/PWM5_2/ADC5/P1.5_12") (pintype "unspecified"))
    )
    (net (code "39") (name "/OLED-SCK") (class "Default")
      (node (ref "H10") (pin "3") (pinfunction "3_3") (pintype "unspecified"))
      (node (ref "RN7") (pin "6") (pinfunction "6_6") (pintype "input"))
      (node (ref "U5") (pin "10") (pinfunction "CCP3/12CSDA/MISO/PWM4_2/ADC4/P1.4_10") (pintype "unspecified"))
    )
    (net (code "40") (name "/OLED-SDA") (class "Default")
      (node (ref "H10") (pin "4") (pinfunction "4_4") (pintype "unspecified"))
      (node (ref "RN7") (pin "5") (pinfunction "5_5") (pintype "input"))
      (node (ref "U5") (pin "11") (pinfunction "TXD_4/RD/P4.4_11") (pintype "unspecified"))
    )
    (net (code "41") (name "/P00") (class "Default")
      (node (ref "J1") (pin "1") (pinfunction "1_1") (pintype "unspecified"))
      (node (ref "U5") (pin "51") (pinfunction "RXD3/ADC8/AD0/P0.0_51") (pintype "unspecified"))
    )
    (net (code "42") (name "/P01") (class "Default")
      (node (ref "J1") (pin "2") (pinfunction "2_2") (pintype "unspecified"))
      (node (ref "U5") (pin "52") (pinfunction "TXD3/ADC9/AD1/P0.1_52") (pintype "unspecified"))
    )
    (net (code "43") (name "/P02") (class "Default")
      (node (ref "J1") (pin "3") (pinfunction "3_3") (pintype "unspecified"))
      (node (ref "U5") (pin "53") (pinfunction "RXD4/ADC10/AD2/P0.2_53") (pintype "unspecified"))
    )
    (net (code "44") (name "/P03") (class "Default")
      (node (ref "J1") (pin "4") (pinfunction "4_4") (pintype "unspecified"))
      (node (ref "U5") (pin "59") (pinfunction "TXD4/ADC11/AD3/P0.3_59") (pintype "unspecified"))
    )
    (net (code "45") (name "/P04") (class "Default")
      (node (ref "J1") (pin "5") (pinfunction "5_5") (pintype "unspecified"))
      (node (ref "U5") (pin "60") (pinfunction "T3/ADC12/AD4/P0.4_60") (pintype "unspecified"))
    )
    (net (code "46") (name "/P05") (class "Default")
      (node (ref "J1") (pin "6") (pinfunction "6_6") (pintype "unspecified"))
      (node (ref "U5") (pin "61") (pinfunction "T3CLKO/ADC13/AD5/P0.5_61") (pintype "unspecified"))
    )
    (net (code "47") (name "/P06") (class "Default")
      (node (ref "J1") (pin "7") (pinfunction "7_7") (pintype "unspecified"))
      (node (ref "U5") (pin "62") (pinfunction "T4/ADC14/AD6/P0.6_62") (pintype "unspecified"))
    )
    (net (code "48") (name "/P07") (class "Default")
      (node (ref "J1") (pin "8") (pinfunction "8_8") (pintype "unspecified"))
      (node (ref "U5") (pin "63") (pinfunction "T4CLK0/AD7/P0.7_63") (pintype "unspecified"))
    )
    (net (code "49") (name "/P10") (class "Default")
      (node (ref "H11") (pin "2") (pinfunction "2_2") (pintype "unspecified"))
      (node (ref "U5") (pin "64") (pinfunction "RXD2/PWM0_2/ADC0/P1.0_64") (pintype "unspecified"))
    )
    (net (code "50") (name "/P11") (class "Default")
      (node (ref "H13") (pin "2") (pinfunction "2_2") (pintype "unspecified"))
      (node (ref "U5") (pin "3") (pinfunction "TXD2/PWM1_2/ADC1/P1.1_3") (pintype "unspecified"))
    )
    (net (code "51") (name "/P12") (class "Default")
      (node (ref "H12") (pin "2") (pinfunction "2_2") (pintype "unspecified"))
      (node (ref "U5") (pin "4") (pinfunction "ADC_ETR/ECI/T2/SS/PWM2_2/ADC2/P1.2_4") (pintype "unspecified"))
    )
    (net (code "52") (name "/P13") (class "Default")
      (node (ref "H14") (pin "2") (pinfunction "2_2") (pintype "unspecified"))
      (node (ref "U5") (pin "5") (pinfunction "T2CLK/MOSI/PWM3_2/ADC3/P1.3_5") (pintype "unspecified"))
    )
    (net (code "53") (name "/P26") (class "Default")
      (node (ref "H2") (pin "4") (pinfunction "4_4") (pintype "unspecified"))
      (node (ref "U5") (pin "49") (pinfunction "CCP3_2/PWM6/A14/P2.6_49") (pintype "unspecified"))
    )
    (net (code "54") (name "/P27") (class "Default")
      (node (ref "H2") (pin "3") (pinfunction "3_3") (pintype "unspecified"))
      (node (ref "U5") (pin "50") (pinfunction "PWM7/A15/P2.7_50") (pintype "unspecified"))
    )
    (net (code "55") (name "/P43") (class "Default")
      (node (ref "H2") (pin "1") (pinfunction "1_1") (pintype "unspecified"))
      (node (ref "U5") (pin "58") (pinfunction "RXD_4/R/P4.3_58") (pintype "unspecified"))
    )
    (net (code "56") (name "/P54") (class "Default")
      (node (ref "R11") (pin "2") (pinfunction "2_2") (pintype "input"))
      (node (ref "U5") (pin "18") (pinfunction "P5.4/RST/MCLKKO_18") (pintype "unspecified"))
    )
    (net (code "57") (name "/P77") (class "Default")
      (node (ref "H2") (pin "2") (pinfunction "2_2") (pintype "unspecified"))
      (node (ref "U5") (pin "57") (pinfunction "12CSCL_3/SCLK_3/P7.7_57") (pintype "unspecified"))
    )
    (net (code "58") (name "/SM1-FAULT") (class "Default")
      (node (ref "RN4") (pin "5") (pinfunction "5_5") (pintype "input"))
      (node (ref "U4") (pin "8") (pinfunction "nFault_8") (pintype "unspecified"))
      (node (ref "U5") (pin "42") (pinfunction "P2.0/A8/PWM0_42") (pintype "unspecified"))
    )
    (net (code "59") (name "/SM1-I1") (class "Default")
      (node (ref "RN3") (pin "8") (pinfunction "8_8") (pintype "input"))
      (node (ref "U4") (pin "16") (pinfunction "AIN1_16") (pintype "unspecified"))
      (node (ref "U5") (pin "38") (pinfunction "P7.0/CCP03_38") (pintype "unspecified"))
    )
    (net (code "60") (name "/SM1-I2") (class "Default")
      (node (ref "RN3") (pin "7") (pinfunction "7_7") (pintype "input"))
      (node (ref "U4") (pin "15") (pinfunction "AIN2_15") (pintype "unspecified"))
      (node (ref "U5") (pin "39") (pinfunction "P7.1/CCP13_39") (pintype "unspecified"))
    )
    (net (code "61") (name "/SM1-I3") (class "Default")
      (node (ref "RN4") (pin "6") (pinfunction "6_6") (pintype "input"))
      (node (ref "U4") (pin "10") (pinfunction "BIN2_10") (pintype "unspecified"))
      (node (ref "U5") (pin "41") (pinfunction "P7.3/CCP33_41") (pintype "unspecified"))
    )
    (net (code "62") (name "/SM1-I4") (class "Default")
      (node (ref "RN4") (pin "7") (pinfunction "7_7") (pintype "input"))
      (node (ref "U4") (pin "9") (pinfunction "BIN1_9") (pintype "unspecified"))
      (node (ref "U5") (pin "40") (pinfunction "P7.2/CCP23_40") (pintype "unspecified"))
    )
    (net (code "63") (name "/SM1-O1") (class "Default")
      (node (ref "C32") (pin "2") (pinfunction "2_2") (pintype "unspecified"))
      (node (ref "H4") (pin "4") (pinfunction "4_4") (pintype "unspecified"))
      (node (ref "U4") (pin "2") (pinfunction "AOUT1_2") (pintype "unspecified"))
    )
    (net (code "64") (name "/SM1-O2") (class "Default")
      (node (ref "C32") (pin "1") (pinfunction "1_1") (pintype "unspecified"))
      (node (ref "H4") (pin "3") (pinfunction "3_3") (pintype "unspecified"))
      (node (ref "U4") (pin "4") (pinfunction "AOUT2_4") (pintype "unspecified"))
    )
    (net (code "65") (name "/SM1-O3") (class "Default")
      (node (ref "C33") (pin "2") (pinfunction "2_2") (pintype "unspecified"))
      (node (ref "H4") (pin "2") (pinfunction "2_2") (pintype "unspecified"))
      (node (ref "U4") (pin "5") (pinfunction "BOUT2_5") (pintype "unspecified"))
    )
    (net (code "66") (name "/SM1-O4") (class "Default")
      (node (ref "C33") (pin "1") (pinfunction "1_1") (pintype "unspecified"))
      (node (ref "H4") (pin "1") (pinfunction "1_1") (pintype "unspecified"))
      (node (ref "U4") (pin "7") (pinfunction "BOUT1_7") (pintype "unspecified"))
    )
    (net (code "67") (name "/SM2-FAULT") (class "Default")
      (node (ref "RN4") (pin "8") (pinfunction "8_8") (pintype "input"))
      (node (ref "U5") (pin "26") (pinfunction "P6.7/PWM7_3_26") (pintype "unspecified"))
      (node (ref "U7") (pin "8") (pinfunction "nFault_8") (pintype "unspecified"))
    )
    (net (code "68") (name "/SM2-I1") (class "Default")
      (node (ref "RN5") (pin "8") (pinfunction "8_8") (pintype "input"))
      (node (ref "U5") (pin "22") (pinfunction "P4.0/WR_3/RXD2_2_22") (pintype "unspecified"))
      (node (ref "U7") (pin "16") (pinfunction "AIN1_16") (pintype "unspecified"))
    )
    (net (code "69") (name "/SM2-I2") (class "Default")
      (node (ref "RN5") (pin "7") (pinfunction "7_7") (pintype "input"))
      (node (ref "U5") (pin "23") (pinfunction "P6.4/PWM4_3_23") (pintype "unspecified"))
      (node (ref "U7") (pin "15") (pinfunction "AIN2_15") (pintype "unspecified"))
    )
    (net (code "70") (name "/SM2-I3") (class "Default")
      (node (ref "RN5") (pin "6") (pinfunction "6_6") (pintype "input"))
      (node (ref "U5") (pin "24") (pinfunction "P6.5/PWM5_3_24") (pintype "unspecified"))
      (node (ref "U7") (pin "10") (pinfunction "BIN2_10") (pintype "unspecified"))
    )
    (net (code "71") (name "/SM2-I4") (class "Default")
      (node (ref "RN5") (pin "5") (pinfunction "5_5") (pintype "input"))
      (node (ref "U5") (pin "25") (pinfunction "P6.6/PWM6_3_25") (pintype "unspecified"))
      (node (ref "U7") (pin "9") (pinfunction "BIN1_9") (pintype "unspecified"))
    )
    (net (code "72") (name "/SM2-O1") (class "Default")
      (node (ref "C34") (pin "2") (pinfunction "2_2") (pintype "unspecified"))
      (node (ref "H1") (pin "4") (pinfunction "4_4") (pintype "unspecified"))
      (node (ref "U7") (pin "2") (pinfunction "AOUT1_2") (pintype "unspecified"))
    )
    (net (code "73") (name "/SM2-O2") (class "Default")
      (node (ref "C34") (pin "1") (pinfunction "1_1") (pintype "unspecified"))
      (node (ref "H1") (pin "3") (pinfunction "3_3") (pintype "unspecified"))
      (node (ref "U7") (pin "4") (pinfunction "AOUT2_4") (pintype "unspecified"))
    )
    (net (code "74") (name "/SM2-O3") (class "Default")
      (node (ref "C35") (pin "2") (pinfunction "2_2") (pintype "unspecified"))
      (node (ref "H1") (pin "2") (pinfunction "2_2") (pintype "unspecified"))
      (node (ref "U7") (pin "5") (pinfunction "BOUT2_5") (pintype "unspecified"))
    )
    (net (code "75") (name "/SM2-O4") (class "Default")
      (node (ref "C35") (pin "1") (pinfunction "1_1") (pintype "unspecified"))
      (node (ref "H1") (pin "1") (pinfunction "1_1") (pintype "unspecified"))
      (node (ref "U7") (pin "7") (pinfunction "BOUT1_7") (pintype "unspecified"))
    )
    (net (code "76") (name "/SW-V") (class "Default")
      (node (ref "LED3") (pin "2") (pinfunction "+_2") (pintype "unspecified"))
      (node (ref "SW1") (pin "3") (pinfunction "3_3") (pintype "unspecified"))
      (node (ref "U1") (pin "3") (pinfunction "VIN_3") (pintype "unspecified"))
    )
    (net (code "77") (name "/U-RXD") (class "Default")
      (node (ref "R12") (pin "2") (pinfunction "2_2") (pintype "input"))
      (node (ref "U2") (pin "7") (pinfunction "RXD_7") (pintype "unspecified"))
    )
    (net (code "78") (name "/U-TXD") (class "Default")
      (node (ref "D1") (pin "1") (pinfunction "C_1") (pintype "unspecified"))
      (node (ref "U2") (pin "6") (pinfunction "TXD_6") (pintype "unspecified"))
    )
    (net (code "79") (name "AGND") (class "Default")
      (node (ref "C11") (pin "2") (pinfunction "2_2") (pintype "unspecified"))
      (node (ref "C12") (pin "1") (pinfunction "1_1") (pintype "unspecified"))
      (node (ref "C24") (pin "2") (pinfunction "2_2") (pintype "input"))
      (node (ref "C25") (pin "2") (pinfunction "2_2") (pintype "input"))
      (node (ref "C26") (pin "2") (pinfunction "2_2") (pintype "input"))
      (node (ref "C27") (pin "2") (pinfunction "2_2") (pintype "input"))
      (node (ref "H11") (pin "1") (pinfunction "1_1") (pintype "unspecified"))
      (node (ref "H12") (pin "1") (pinfunction "1_1") (pintype "unspecified"))
      (node (ref "H13") (pin "1") (pinfunction "1_1") (pintype "unspecified"))
      (node (ref "H14") (pin "1") (pinfunction "1_1") (pintype "unspecified"))
      (node (ref "R8") (pin "1") (pinfunction "1_1") (pintype "input"))
      (node (ref "U5") (pin "15") (pinfunction "ADC_Agnd_15") (pintype "unspecified"))
      (node (ref "U6") (pin "3") (pinfunction "A_3") (pintype "unspecified"))
    )
    (net (code "80") (name "GND") (class "Default")
      (node (ref "C1") (pin "2") (pinfunction "2_2") (pintype "unspecified"))
      (node (ref "C10") (pin "1") (pinfunction "1_1") (pintype "unspecified"))
      (node (ref "C16") (pin "1") (pinfunction "1_1") (pintype "input"))
      (node (ref "C17") (pin "1") (pinfunction "1_1") (pintype "input"))
      (node (ref "C2") (pin "2") (pinfunction "2_2") (pintype "unspecified"))
      (node (ref "C22") (pin "1") (pinfunction "1_1") (pintype "input"))
      (node (ref "C23") (pin "1") (pinfunction "1_1") (pintype "input"))
      (node (ref "C29") (pin "2") (pinfunction "2_2") (pintype "input"))
      (node (ref "C3") (pin "2") (pinfunction "2_2") (pintype "unspecified"))
      (node (ref "C4") (pin "1") (pinfunction "1_1") (pintype "unspecified"))
      (node (ref "C5") (pin "1") (pinfunction "1_1") (pintype "unspecified"))
      (node (ref "C9") (pin "1") (pinfunction "1_1") (pintype "input"))
      (node (ref "H10") (pin "1") (pinfunction "1_1") (pintype "unspecified"))
      (node (ref "H15") (pin "10") (pinfunction "10_10") (pintype "unspecified"))
      (node (ref "H15") (pin "2") (pinfunction "2_2") (pintype "unspecified"))
      (node (ref "H15") (pin "4") (pinfunction "4_4") (pintype "unspecified"))
      (node (ref "H15") (pin "6") (pinfunction "6_6") (pintype "unspecified"))
      (node (ref "H15") (pin "8") (pinfunction "8_8") (pintype "unspecified"))
      (node (ref "KEY1") (pin "4") (pinfunction "4_4") (pintype "unspecified"))
      (node (ref "MK1") (pin "8") (pinfunction "GND_8") (pintype "unspecified"))
      (node (ref "MPU1") (pin "10") (pinfunction "FSYNC_10") (pintype "unspecified"))
      (node (ref "MPU1") (pin "2") (pinfunction "GND_2") (pintype "unspecified"))
      (node (ref "MPU1") (pin "7") (pinfunction "ADO_7") (pintype "unspecified"))
      (node (ref "Q1") (pin "2") (pinfunction "2_2") (pintype "input"))
      (node (ref "Q2") (pin "2") (pinfunction "2_2") (pintype "input"))
      (node (ref "R1") (pin "1") (pinfunction "1_1") (pintype "input"))
      (node (ref "R13") (pin "2") (pinfunction "2_2") (pintype "input"))
      (node (ref "R2") (pin "1") (pinfunction "1_1") (pintype "input"))
      (node (ref "R5") (pin "2") (pinfunction "2_2") (pintype "input"))
      (node (ref "R6") (pin "2") (pinfunction "2_2") (pintype "input"))
      (node (ref "R7") (pin "2") (pinfunction "2_2") (pintype "input"))
      (node (ref "U1") (pin "1") (pinfunction "ADJ/GND_1") (pintype "unspecified"))
      (node (ref "U3") (pin "11") (pinfunction "GND_11") (pintype "unspecified"))
      (node (ref "U3") (pin "2") (pinfunction "GND_2") (pintype "unspecified"))
      (node (ref "U3") (pin "3") (pinfunction "GND_3") (pintype "unspecified"))
      (node (ref "U3") (pin "4") (pinfunction "GND_4") (pintype "unspecified"))
      (node (ref "U3") (pin "6") (pinfunction "GND_6") (pintype "unspecified"))
      (node (ref "U5") (pin "21") (pinfunction "GND_21") (pintype "unspecified"))
      (node (ref "U8") (pin "1") (pinfunction "1_1") (pintype "unspecified"))
      (node (ref "U8") (pin "2") (pinfunction "2_2") (pintype "unspecified"))
    )
    (net (code "81") (name "Net-(D1-A)") (class "Default")
      (node (ref "D1") (pin "2") (pinfunction "A_2") (pintype "unspecified"))
      (node (ref "U5") (pin "27") (pinfunction "P3.0/RXD/CCP3_4/INT4_27") (pintype "unspecified"))
    )
    (net (code "82") (name "Net-(KEY1-Pad1)") (class "Default")
      (node (ref "KEY1") (pin "1") (pinfunction "1_1") (pintype "unspecified"))
      (node (ref "R11") (pin "1") (pinfunction "1_1") (pintype "input"))
    )
    (net (code "83") (name "Net-(LED1--)") (class "Default")
      (node (ref "LED1") (pin "1") (pinfunction "-_1") (pintype "unspecified"))
      (node (ref "R5") (pin "1") (pinfunction "1_1") (pintype "input"))
    )
    (net (code "84") (name "Net-(LED2--)") (class "Default")
      (node (ref "LED2") (pin "1") (pinfunction "-_1") (pintype "unspecified"))
      (node (ref "R6") (pin "1") (pinfunction "1_1") (pintype "input"))
    )
    (net (code "85") (name "Net-(LED3--)") (class "Default")
      (node (ref "LED3") (pin "1") (pinfunction "-_1") (pintype "unspecified"))
      (node (ref "R13") (pin "1") (pinfunction "1_1") (pintype "input"))
    )
    (net (code "86") (name "Net-(Q1-Pad1)") (class "Default")
      (node (ref "Q1") (pin "1") (pinfunction "1_1") (pintype "input"))
      (node (ref "R1") (pin "2") (pinfunction "2_2") (pintype "input"))
      (node (ref "R3") (pin "2") (pinfunction "2_2") (pintype "input"))
    )
    (net (code "87") (name "Net-(Q2-Pad1)") (class "Default")
      (node (ref "Q2") (pin "1") (pinfunction "1_1") (pintype "input"))
      (node (ref "R2") (pin "2") (pinfunction "2_2") (pintype "input"))
      (node (ref "R4") (pin "2") (pinfunction "2_2") (pintype "input"))
    )
    (net (code "88") (name "Net-(U2-V3)") (class "Default")
      (node (ref "C36") (pin "2") (pinfunction "2_2") (pintype "unspecified"))
      (node (ref "U2") (pin "8") (pinfunction "V3_8") (pintype "unspecified"))
    )
    (net (code "89") (name "Net-(U4-VCP)") (class "Default")
      (node (ref "C8") (pin "2") (pinfunction "2_2") (pintype "unspecified"))
      (node (ref "U4") (pin "11") (pinfunction "VCP_11") (pintype "unspecified"))
    )
    (net (code "90") (name "Net-(U4-VINT)") (class "Default")
      (node (ref "C7") (pin "1") (pinfunction "1_1") (pintype "input"))
      (node (ref "U4") (pin "14") (pinfunction "VINT_14") (pintype "unspecified"))
    )
    (net (code "91") (name "Net-(U5-P3.1{slash}TXD{slash}CCP2_4)") (class "Default")
      (node (ref "R12") (pin "1") (pinfunction "1_1") (pintype "input"))
      (node (ref "U5") (pin "28") (pinfunction "P3.1/TXD/CCP2_4_28") (pintype "unspecified"))
    )
    (net (code "92") (name "Net-(U7-VCP)") (class "Default")
      (node (ref "C15") (pin "2") (pinfunction "2_2") (pintype "unspecified"))
      (node (ref "U7") (pin "11") (pinfunction "VCP_11") (pintype "unspecified"))
    )
    (net (code "93") (name "Net-(U7-VINT)") (class "Default")
      (node (ref "C14") (pin "1") (pinfunction "1_1") (pintype "input"))
      (node (ref "U7") (pin "14") (pinfunction "VINT_14") (pintype "unspecified"))
    )
    (net (code "94") (name "SGND") (class "Default")
      (node (ref "C13") (pin "2") (pinfunction "2_2") (pintype "unspecified"))
      (node (ref "C14") (pin "2") (pinfunction "2_2") (pintype "input"))
      (node (ref "C19") (pin "2") (pinfunction "2_2") (pintype "unspecified"))
      (node (ref "C20") (pin "2") (pinfunction "2_2") (pintype "unspecified"))
      (node (ref "C28") (pin "2") (pinfunction "2_2") (pintype "input"))
      (node (ref "C30") (pin "2") (pinfunction "2_2") (pintype "input"))
      (node (ref "C31") (pin "2") (pinfunction "2_2") (pintype "input"))
      (node (ref "C36") (pin "1") (pinfunction "1_1") (pintype "unspecified"))
      (node (ref "C37") (pin "1") (pinfunction "1_1") (pintype "unspecified"))
      (node (ref "C6") (pin "2") (pinfunction "2_2") (pintype "unspecified"))
      (node (ref "C7") (pin "2") (pinfunction "2_2") (pintype "input"))
      (node (ref "R7") (pin "1") (pinfunction "1_1") (pintype "input"))
      (node (ref "R8") (pin "2") (pinfunction "2_2") (pintype "input"))
      (node (ref "U10") (pin "3") (pinfunction "GND_3") (pintype "unspecified"))
      (node (ref "U11") (pin "3") (pinfunction "3_3") (pintype "unspecified"))
      (node (ref "U11") (pin "4") (pinfunction "4_4") (pintype "unspecified"))
      (node (ref "U2") (pin "3") (pinfunction "GND_3") (pintype "unspecified"))
      (node (ref "U4") (pin "13") (pinfunction "GND_13") (pintype "unspecified"))
      (node (ref "U4") (pin "17") (pinfunction "GND_17") (pintype "unspecified"))
      (node (ref "U4") (pin "3") (pinfunction "AISEN_3") (pintype "unspecified"))
      (node (ref "U4") (pin "6") (pinfunction "BISEN_6") (pintype "unspecified"))
      (node (ref "U7") (pin "13") (pinfunction "GND_13") (pintype "unspecified"))
      (node (ref "U7") (pin "17") (pinfunction "GND_17") (pintype "unspecified"))
      (node (ref "U7") (pin "3") (pinfunction "AISEN_3") (pintype "unspecified"))
      (node (ref "U7") (pin "6") (pinfunction "BISEN_6") (pintype "unspecified"))
      (node (ref "U8") (pin "5") (pinfunction "5_5") (pintype "unspecified"))
      (node (ref "U8") (pin "6") (pinfunction "6_6") (pintype "unspecified"))
      (node (ref "U9") (pin "3") (pinfunction "GND_3") (pintype "unspecified"))
      (node (ref "USB1") (pin "4") (pinfunction "ID_4") (pintype "unspecified"))
      (node (ref "USB1") (pin "5") (pinfunction "GND_5") (pintype "unspecified"))
    )
    (net (code "95") (name "VCC") (class "Default")
      (node (ref "C1") (pin "1") (pinfunction "1_1") (pintype "unspecified"))
      (node (ref "C10") (pin "2") (pinfunction "2_2") (pintype "unspecified"))
      (node (ref "C2") (pin "1") (pinfunction "1_1") (pintype "unspecified"))
      (node (ref "C29") (pin "1") (pinfunction "1_1") (pintype "input"))
      (node (ref "C3") (pin "1") (pinfunction "1_1") (pintype "unspecified"))
      (node (ref "C4") (pin "2") (pinfunction "2_2") (pintype "unspecified"))
      (node (ref "C5") (pin "2") (pinfunction "2_2") (pintype "unspecified"))
      (node (ref "H10") (pin "2") (pinfunction "2_2") (pintype "unspecified"))
      (node (ref "MK1") (pin "1") (pinfunction "VCC_1") (pintype "unspecified"))
      (node (ref "MPU1") (pin "1") (pinfunction "VCC_1") (pintype "unspecified"))
      (node (ref "R9") (pin "1") (pinfunction "1_1") (pintype "input"))
      (node (ref "RN1") (pin "1") (pinfunction "1_1") (pintype "input"))
      (node (ref "RN1") (pin "2") (pinfunction "2_2") (pintype "input"))
      (node (ref "RN1") (pin "3") (pinfunction "3_3") (pintype "input"))
      (node (ref "RN1") (pin "4") (pinfunction "4_4") (pintype "input"))
      (node (ref "RN2") (pin "1") (pinfunction "1_1") (pintype "input"))
      (node (ref "RN2") (pin "2") (pinfunction "2_2") (pintype "input"))
      (node (ref "RN2") (pin "3") (pinfunction "3_3") (pintype "input"))
      (node (ref "RN2") (pin "4") (pinfunction "4_4") (pintype "input"))
      (node (ref "RN3") (pin "1") (pinfunction "1_1") (pintype "input"))
      (node (ref "RN3") (pin "2") (pinfunction "2_2") (pintype "input"))
      (node (ref "RN3") (pin "3") (pinfunction "3_3") (pintype "input"))
      (node (ref "RN3") (pin "4") (pinfunction "4_4") (pintype "input"))
      (node (ref "RN4") (pin "1") (pinfunction "1_1") (pintype "input"))
      (node (ref "RN4") (pin "2") (pinfunction "2_2") (pintype "input"))
      (node (ref "RN4") (pin "3") (pinfunction "3_3") (pintype "input"))
      (node (ref "RN4") (pin "4") (pinfunction "4_4") (pintype "input"))
      (node (ref "RN5") (pin "1") (pinfunction "1_1") (pintype "input"))
      (node (ref "RN5") (pin "2") (pinfunction "2_2") (pintype "input"))
      (node (ref "RN5") (pin "3") (pinfunction "3_3") (pintype "input"))
      (node (ref "RN5") (pin "4") (pinfunction "4_4") (pintype "input"))
      (node (ref "RN6") (pin "1") (pinfunction "1_1") (pintype "input"))
      (node (ref "RN6") (pin "2") (pinfunction "2_2") (pintype "input"))
      (node (ref "RN6") (pin "3") (pinfunction "3_3") (pintype "input"))
      (node (ref "RN6") (pin "4") (pinfunction "4_4") (pintype "input"))
      (node (ref "RN7") (pin "1") (pinfunction "1_1") (pintype "input"))
      (node (ref "RN7") (pin "2") (pinfunction "2_2") (pintype "input"))
      (node (ref "RN7") (pin "3") (pinfunction "3_3") (pintype "input"))
      (node (ref "RN7") (pin "4") (pinfunction "4_4") (pintype "input"))
      (node (ref "RN8") (pin "1") (pinfunction "1_1") (pintype "input"))
      (node (ref "RN8") (pin "2") (pinfunction "2_2") (pintype "input"))
      (node (ref "RN8") (pin "3") (pinfunction "3_3") (pintype "input"))
      (node (ref "RN8") (pin "4") (pinfunction "4_4") (pintype "input"))
      (node (ref "RN9") (pin "1") (pinfunction "1_1") (pintype "input"))
      (node (ref "RN9") (pin "2") (pinfunction "2_2") (pintype "input"))
      (node (ref "RN9") (pin "3") (pinfunction "3_3") (pintype "input"))
      (node (ref "RN9") (pin "4") (pinfunction "4_4") (pintype "input"))
      (node (ref "U1") (pin "2") (pinfunction "VOUT_2") (pintype "unspecified"))
      (node (ref "U3") (pin "7") (pinfunction "VCC_7") (pintype "unspecified"))
      (node (ref "U5") (pin "19") (pinfunction "VCC_19") (pintype "unspecified"))
      (node (ref "U8") (pin "3") (pinfunction "3_3") (pintype "unspecified"))
      (node (ref "U8") (pin "4") (pinfunction "4_4") (pintype "unspecified"))
    )
    (net (code "96") (name "VM1") (class "Default")
      (node (ref "C19") (pin "1") (pinfunction "1_1") (pintype "unspecified"))
      (node (ref "C30") (pin "1") (pinfunction "1_1") (pintype "input"))
      (node (ref "C6") (pin "1") (pinfunction "1_1") (pintype "unspecified"))
      (node (ref "C8") (pin "1") (pinfunction "1_1") (pintype "unspecified"))
      (node (ref "U11") (pin "1") (pinfunction "1_1") (pintype "unspecified"))
      (node (ref "U4") (pin "12") (pinfunction "VM_12") (pintype "unspecified"))
      (node (ref "U9") (pin "4") (pinfunction "VCC_4") (pintype "unspecified"))
    )
    (net (code "97") (name "VM2") (class "Default")
      (node (ref "C13") (pin "1") (pinfunction "1_1") (pintype "unspecified"))
      (node (ref "C15") (pin "1") (pinfunction "1_1") (pintype "unspecified"))
      (node (ref "C20") (pin "1") (pinfunction "1_1") (pintype "unspecified"))
      (node (ref "C31") (pin "1") (pinfunction "1_1") (pintype "input"))
      (node (ref "U10") (pin "4") (pinfunction "VCC_4") (pintype "unspecified"))
      (node (ref "U11") (pin "2") (pinfunction "2_2") (pintype "unspecified"))
      (node (ref "U7") (pin "12") (pinfunction "VM_12") (pintype "unspecified"))
    )
    (net (code "98") (name "Vin") (class "Default")
      (node (ref "C28") (pin "1") (pinfunction "1_1") (pintype "input"))
      (node (ref "C37") (pin "2") (pinfunction "2_2") (pintype "unspecified"))
      (node (ref "SW1") (pin "2") (pinfunction "2_2") (pintype "unspecified"))
      (node (ref "U2") (pin "5") (pinfunction "VCC_5") (pintype "unspecified"))
      (node (ref "U8") (pin "7") (pinfunction "7_7") (pintype "unspecified"))
      (node (ref "U8") (pin "8") (pinfunction "8_8") (pintype "unspecified"))
      (node (ref "USB1") (pin "1") (pinfunction "VBUS_1") (pintype "unspecified"))
    )
    (net (code "99") (name "unconnected-(KEY1-Pad2)") (class "Default")
      (node (ref "KEY1") (pin "2") (pinfunction "2_2") (pintype "unspecified+no_connect"))
    )
    (net (code "100") (name "unconnected-(KEY1-Pad3)") (class "Default")
      (node (ref "KEY1") (pin "3") (pinfunction "3_3") (pintype "unspecified+no_connect"))
    )
    (net (code "101") (name "unconnected-(MPU1-ECL-Pad6)") (class "Default")
      (node (ref "MPU1") (pin "6") (pinfunction "ECL_6") (pintype "unspecified+no_connect"))
    )
    (net (code "102") (name "unconnected-(MPU1-EDA-Pad5)") (class "Default")
      (node (ref "MPU1") (pin "5") (pinfunction "EDA_5") (pintype "unspecified+no_connect"))
    )
    (net (code "103") (name "unconnected-(MPU1-INT-Pad8)") (class "Default")
      (node (ref "MPU1") (pin "8") (pinfunction "INT_8") (pintype "unspecified+no_connect"))
    )
    (net (code "104") (name "unconnected-(MPU1-NCS-Pad9)") (class "Default")
      (node (ref "MPU1") (pin "9") (pinfunction "NCS_9") (pintype "unspecified+no_connect"))
    )
    (net (code "105") (name "unconnected-(SW1-Pad1)") (class "Default")
      (node (ref "SW1") (pin "1") (pinfunction "1_1") (pintype "unspecified+no_connect"))
    )
    (net (code "106") (name "unconnected-(SW1-PadEH)") (class "Default")
      (node (ref "SW1") (pin "EH") (pinfunction "EH_EH") (pintype "unspecified+no_connect"))
    )
    (net (code "107") (name "unconnected-(U1-VOUT-Pad4)") (class "Default")
      (node (ref "U1") (pin "4") (pinfunction "VOUT_4") (pintype "unspecified+no_connect"))
    )
    (net (code "108") (name "unconnected-(U2-RTS#-Pad4)") (class "Default")
      (node (ref "U2") (pin "4") (pinfunction "RTS#_4") (pintype "unspecified+no_connect"))
    )
    (net (code "109") (name "unconnected-(U3-P0_0-Pad12)") (class "Default")
      (node (ref "U3") (pin "12") (pinfunction "P0_0_12") (pintype "unspecified+no_connect"))
    )
    (net (code "110") (name "unconnected-(U3-RF-Pad1)") (class "Default")
      (node (ref "U3") (pin "1") (pinfunction "RF_1") (pintype "unspecified+no_connect"))
    )
    (net (code "111") (name "unconnected-(U4-nSleep-Pad1)") (class "Default")
      (node (ref "U4") (pin "1") (pinfunction "nSleep_1") (pintype "unspecified+no_connect"))
    )
    (net (code "112") (name "unconnected-(U7-nSleep-Pad1)") (class "Default")
      (node (ref "U7") (pin "1") (pinfunction "nSleep_1") (pintype "unspecified+no_connect"))
    )
    (net (code "113") (name "unconnected-(U9-BO-Pad7)") (class "Default")
      (node (ref "U9") (pin "7") (pinfunction "BO_7") (pintype "unspecified+no_connect"))
    )
    (net (code "114") (name "unconnected-(U9-FO-Pad6)") (class "Default")
      (node (ref "U9") (pin "6") (pinfunction "FO_6") (pintype "unspecified+no_connect"))
    )
    (net (code "115") (name "unconnected-(U10-BO-Pad7)") (class "Default")
      (node (ref "U10") (pin "7") (pinfunction "BO_7") (pintype "unspecified+no_connect"))
    )
    (net (code "116") (name "unconnected-(U10-FO-Pad6)") (class "Default")
      (node (ref "U10") (pin "6") (pinfunction "FO_6") (pintype "unspecified+no_connect"))
    )
    (net (code "117") (name "unconnected-(USB1-SH1-Pad6)") (class "Default")
      (node (ref "USB1") (pin "6") (pinfunction "SH1_6") (pintype "unspecified+no_connect"))
    )
    (net (code "118") (name "unconnected-(USB1-SH2-Pad7)") (class "Default")
      (node (ref "USB1") (pin "7") (pinfunction "SH2_7") (pintype "unspecified+no_connect"))
    )
    (net (code "119") (name "unconnected-(USB1-SH3-Pad8)") (class "Default")
      (node (ref "USB1") (pin "8") (pinfunction "SH3_8") (pintype "unspecified+no_connect"))
    )
    (net (code "120") (name "unconnected-(USB1-SH4-Pad9)") (class "Default")
      (node (ref "USB1") (pin "9") (pinfunction "SH4_9") (pintype "unspecified+no_connect"))
    )
  )
)
